# 24V_DCDC_Conv.net
KiCad netlist of a schematic drawn in Altium Designer
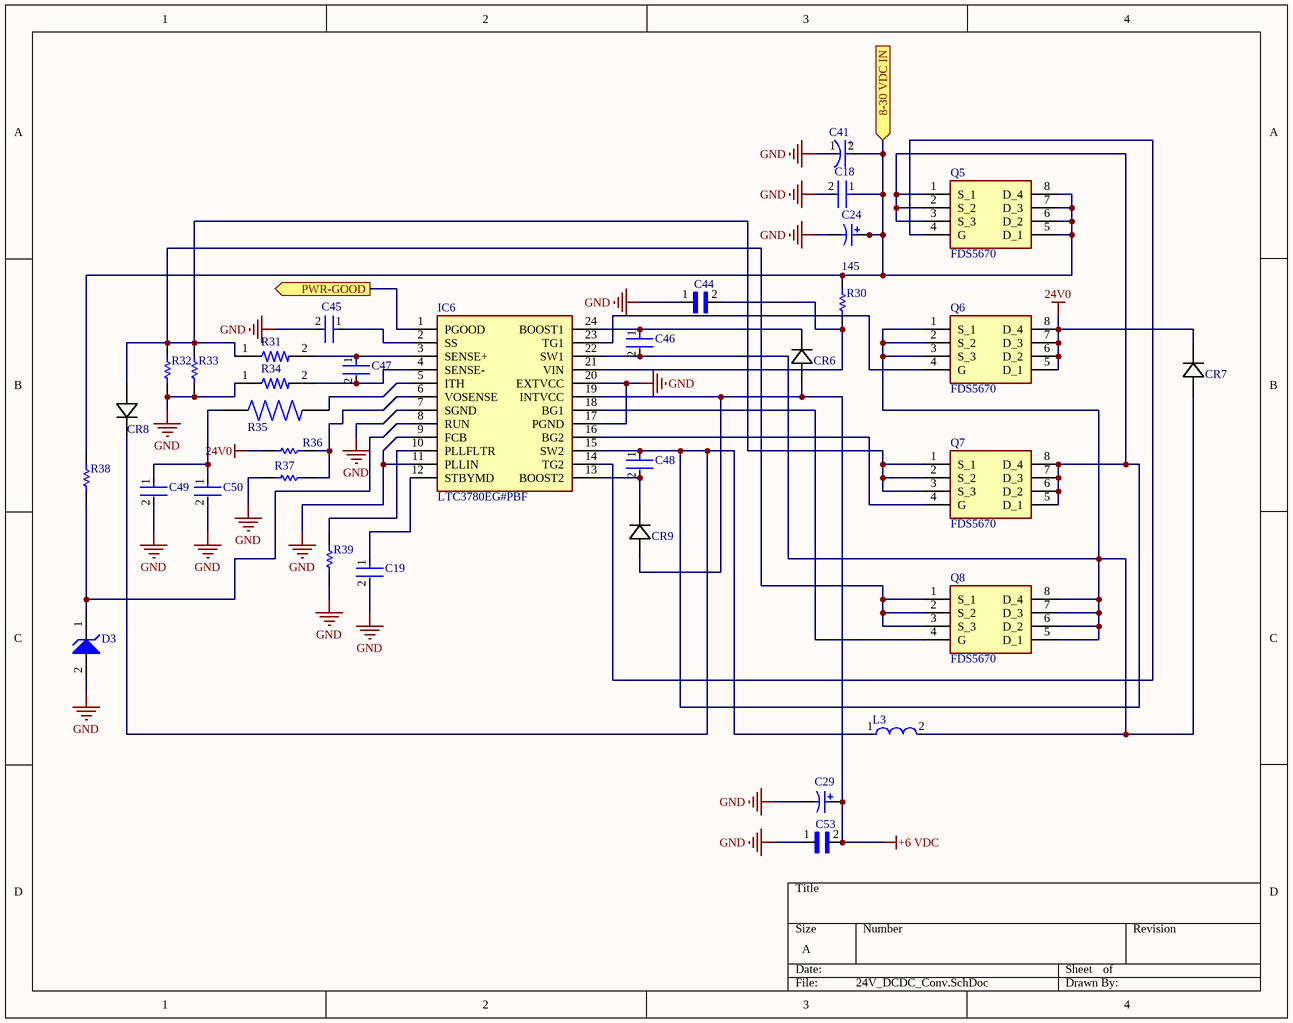
[diagram p0: 24V_DCDC_Conv.SchDoc]

(export (version "E")
  (design (tool "Eeschema 10.0.6"))
  (components
    (comp (ref "C18")
      (value "C0603C104K5RACTU")
      (footprint "FP-C0603C-CF-IPC_A")
      (description "Multilayer Ceramic Capacitors (MLCC) - SMD/SMT 50volts 0.1uF X7R 10%")
      (fields (field (name "MANUFACTURER") "KEMET") (field (name "TOLERANCE") "10%"))
      (libsource (lib "Replacements") (part "C0603C104K5RACTU"))
    )
    (comp (ref "C19")
      (value "C0603C104K5RACTU")
      (footprint "FP-C0603C-CF-IPC_A")
      (description "Multilayer Ceramic Capacitors (MLCC) - SMD/SMT 50volts 0.1uF X7R 10%")
      (fields (field (name "MANUFACTURER") "KEMET") (field (name "TOLERANCE") "10%"))
      (libsource (lib "Replacements") (part "C0603C104K5RACTU"))
    )
    (comp (ref "C24")
      (value "UUD1V220MCL1GS")
      (footprint "NIC-CAPA2-5X5.8_V")
      (description "Aluminum Electrolytic Capacitor, 22uF 35 V, UD Series 2000h 5 (Dia.) x 5.8mm")
      (fields
        (field (name "MANUFACTURER") "Nichicon")
        (field (name "TOLERANCE") "20%")
        (field (name "STOCK 1") "145")
      )
      (libsource (lib "Replacements") (part "UUD1V220MCL1GS"))
    )
    (comp (ref "C29")
      (value "UUD1V4R7MCL1GS")
      (footprint "NIC-CAPA2-4X5.8_V")
      (description "Cap Aluminum Lytic 4.7uF 35V 20% (4 X 5.8mm) SMD 80mA 2000h 105C Automotive T/R")
      (fields (field (name "MANUFACTURER") "Nichicon") (field (name "TOLERANCE") "20%"))
      (libsource (lib "Replacements") (part "UUD1V4R7MCL1GS"))
    )
    (comp (ref "C41")
      (value "EEE-HA1E221UP")
      (footprint "FP-HAF-MFG")
      (description "CAP ALUM 220UF 20% 25V SMD")
      (fields
        (field (name "VOLTAGE") "25V")
        (field (name "OCTOPART") "https://octopart.com/eee-ha1e221up-panasonic-39481261")
      )
      (libsource (lib "Altium Content Vault") (part "a00bbbee19879c290e62620ae7e47b1"))
    )
    (comp (ref "C44")
      (value "C0805C104M5UACTU")
      (footprint "CAPC2012X88N")
      (description "0.1ÂµF Â±20% 50V Ceramic Capacitor Z5U 0805 _2012 Metric_")
      (fields (field (name "MF") "KEMET"))
      (libsource (lib "0.1uF_Cap_C0805C104M5UACTU") (part "C0805C104M5UACTU"))
    )
    (comp (ref "C45")
      (value "CC0805KRX7R9BB223")
      (footprint "FP-CC0805-0_85-IPC_C")
      (description "CAP CER 0.022UF 50V X7R 0805")
      (fields
        (field (name "OCTOPART") "https://octopart.com/cc0805krx7r9bb223-yageo-39467761")
        (field (name "MANUFACTURER") "Yageo")
      )
      (libsource (lib "Altium Content Vault") (part "11868f565c42a9108669ba33697ecf6"))
    )
    (comp (ref "C46")
      (value "C0805C224K5RACTU")
      (footprint "FP-C0805C-DN-IPC_A")
      (description "CAP CER 0.22UF 50V X7R 0805")
      (fields
        (field (name "MANUFACTURER") "KEMET")
        (field (name "OCTOPART") "https://octopart.com/c0805c224k5ractu-kemet-144670")
      )
      (libsource (lib "Altium Content Vault") (part "b4654b650e69147ec39a6b967a45e02"))
    )
    (comp (ref "C47")
      (value "C1206C680J5GACTU")
      (footprint "FP-C1206C-EB-MFG")
      (description "1206 C 68pF Ceramic Multilayer Capacitor; 50 VDC; +125degC; C0G Dielec; +/-5%")
      (fields
        (field (name "OCTOPART") "https://octopart.com/c1206c680j5gactu-kemet-138975")
        (field (name "TOLERANCE") "0.05")
      )
      (libsource (lib "Altium Content Vault") (part "b4654b650e69147ec39a6b967a45e02"))
    )
    (comp (ref "C48")
      (value "C0805C224K5RACTU")
      (footprint "FP-C0805C-DN-MFG")
      (description "CAP CER 0.22UF 50V X7R 0805")
      (fields
        (field (name "MANUFACTURER") "KEMET")
        (field (name "OCTOPART") "https://octopart.com/c0805c224k5ractu-kemet-144670")
      )
      (libsource (lib "0.22uF_Cap_C0805C224K5RACTU") (part "CMP-1036-04552-2"))
    )
    (comp (ref "C49")
      (value "C1206C470J5GACTU")
      (footprint "FP-C1206C-EB-MFG")
      (description "CAP CER 47PF 50V C0G/NP0 1206")
      (fields
        (field (name "TOLERANCE") "0.05")
        (field (name "OCTOPART") "https://octopart.com/c1206c470j5gactu-kemet-96509")
      )
      (libsource (lib "47pF_Cap_C1206C470J5GACTU") (part "CMP-03020-017724-1"))
    )
    (comp (ref "C50")
      (value "CC0603KRX7R9BB103")
      (footprint "FP-CC0603-DA-IPC_B")
      (description "CAP CER 10000PF 50V X7R 0603")
      (fields (field (name "TOLERANCE") "0.1") (field (name "MANUFACTURER") "YAGEO"))
      (libsource (lib "Altium Content Vault") (part "11868f565c42a9108669ba33697ecf6"))
    )
    (comp (ref "C53")
      (value "C0805C104M5UACTU")
      (footprint "CAPC2012X88N")
      (description "0.1ÂµF Â±20% 50V Ceramic Capacitor Z5U 0805 _2012 Metric_")
      (fields (field (name "MF") "KEMET"))
      (libsource (lib "0.1uF_Cap_C0805C104M5UACTU") (part "C0805C104M5UACTU"))
    )
    (comp (ref "CR6")
      (value "SS34-E3/9AT")
      (footprint "CR_3/9AT_VIS")
      (description "No Description Available")
      (fields (field (name "COPYRIGHT") "Copyright (C) 2021 Ultra Librarian. All rights reserved."))
      (libsource (lib "SS34-E3_slash_9AT") (part "SS34-E3/9AT"))
    )
    (comp (ref "CR7")
      (value "SS34-E3/9AT")
      (footprint "CR_3/9AT_VIS")
      (description "No Description Available")
      (fields (field (name "COPYRIGHT") "Copyright (C) 2021 Ultra Librarian. All rights reserved."))
      (libsource (lib "SS34-E3_slash_9AT") (part "SS34-E3/9AT"))
    )
    (comp (ref "CR8")
      (value "SS34-E3/9AT")
      (footprint "CR_3/9AT_VIS")
      (description "No Description Available")
      (fields (field (name "COPYRIGHT") "Copyright (C) 2021 Ultra Librarian. All rights reserved."))
      (libsource (lib "SS34-E3_slash_9AT") (part "SS34-E3/9AT"))
    )
    (comp (ref "CR9")
      (value "SS34-E3/9AT")
      (footprint "CR_3/9AT_VIS")
      (description "No Description Available")
      (fields (field (name "COPYRIGHT") "Copyright (C) 2021 Ultra Librarian. All rights reserved."))
      (libsource (lib "SS34-E3_slash_9AT") (part "SS34-E3/9AT"))
    )
    (comp (ref "D3")
      (value "MMSZ4689T1G")
      (footprint "ONSC-SOD-123-2-425-04_V")
      (description "Zener Voltage Regulator, 500 mW, 2-Pin SOD-123, Pb-Free, Tape and Reel")
      (fields (field (name "MANUFACTURER") "On Semiconductor"))
      (libsource (lib "Altium Content Vault") (part "ONSC-K1A2-2"))
    )
    (comp (ref "IC6")
      (value "LTC3780EG#PBF")
      (footprint "SOP65P780X200-24N")
      (description "Integrated Circuit")
      (fields (field (name "MOUSER PART NUMBER") "584-LTC3780EG#PBF"))
      (libsource (lib "SamacSys") (part "LTC3780EG#PBF"))
    )
    (comp (ref "L3")
      (value "IHLP5050CEER4R7M01")
      (footprint "FP-IHLP-5050CE-FP_3_175x3-MFG")
      (description "Commercial Inductors, High Saturation Series 4.7uH 10A 15mΩ 20%")
      (fields (field (name "TOLERANCE") "20%"))
      (libsource (lib "Altium Content Vault") (part "725321dda6339637d4d059423bc1c3c"))
    )
    (comp (ref "Q5")
      (value "FDS5670")
      (footprint "SOIC127P600X175-8N")
      (description "MOSFET (N-Channel)")
      (fields (field (name "MOUSER PART NUMBER") "512-FDS5670"))
      (libsource (lib "SamacSys") (part "FDS5670"))
    )
    (comp (ref "Q6")
      (value "FDS5670")
      (footprint "SOIC127P600X175-8N")
      (description "MOSFET (N-Channel)")
      (fields (field (name "MOUSER PART NUMBER") "512-FDS5670"))
      (libsource (lib "SamacSys") (part "FDS5670"))
    )
    (comp (ref "Q7")
      (value "FDS5670")
      (footprint "SOIC127P600X175-8N")
      (description "MOSFET (N-Channel)")
      (fields (field (name "MOUSER PART NUMBER") "512-FDS5670"))
      (libsource (lib "SamacSys") (part "FDS5670"))
    )
    (comp (ref "Q8")
      (value "FDS5670")
      (footprint "SOIC127P600X175-8N")
      (description "MOSFET (N-Channel)")
      (fields (field (name "MOUSER PART NUMBER") "512-FDS5670"))
      (libsource (lib "SamacSys") (part "FDS5670"))
    )
    (comp (ref "R30")
      (value "ERJ3EKF1002V")
      (footprint "RESC1609X55X30LL15T15")
      (description "Chip Resistor, 10 KOhm, +/- 1%, 0.1 W, -55 to 155 degC, 0603 (1608 Metric), RoHS, Tape and Reel")
      (fields (field (name "TOLERANCE") "1%") (field (name "MANUFACTURER") "Panasonic"))
      (libsource (lib "10k_Res_ERJ-3EKF1002V") (part "CMP-1012-00623-3"))
    )
    (comp (ref "R31")
      (value "CRGS0805J100R")
      (footprint "RESC2012X65N")
      (description "100 Ohms Â±5% 0.5W, 1/2W Chip Resistor 0805 _2012 Metric_ Pulse Withstanding Thick Film")
      (fields (field (name "MF") "TE Connectivity"))
      (libsource (lib "100_Res_CRGS0805J100R") (part "CRGS0805J100R"))
    )
    (comp (ref "R32")
      (value "ERJ8BWFR018V")
      (footprint "RESC3216X70X50NL05T20")
      (fields (field (name "MANUFACTURER") "Panasonic"))
      (libsource (lib "18m_Resistor_ERJ-8BWFR018V") (part "CMP-2003-00769-1"))
    )
    (comp (ref "R33")
      (value "ERJ8BWFR018V")
      (footprint "RESC3216X70X50NL05T20")
      (fields (field (name "MANUFACTURER") "Panasonic"))
      (libsource (lib "18m_Resistor_ERJ-8BWFR018V") (part "CMP-2003-00769-1"))
    )
    (comp (ref "R34")
      (value "CRGS0805J100R")
      (footprint "RESC2012X65N")
      (description "100 Ohms Â±5% 0.5W, 1/2W Chip Resistor 0805 _2012 Metric_ Pulse Withstanding Thick Film")
      (fields (field (name "MF") "TE Connectivity"))
      (libsource (lib "100_Res_CRGS0805J100R") (part "CRGS0805J100R"))
    )
    (comp (ref "R35")
      (value "RC1206JR-07100KL")
      (footprint "RESC3116X65N")
      (description "Carbon film resistor 100 kâ„¦ SMD 1206 0.25 W 5 % 200 ppm Yageo RC1206JR-07100KL 1 pc(s)")
      (libsource (lib "100K_Res_RC1206JR-07100KL") (part "RC1206JR-07100KL"))
    )
    (comp (ref "R36")
      (value "CRCW1206294KFKEA")
      (footprint "RESC3216X60X45ML10T20")
      (fields (field (name "MANUFACTURER") "Vishay Dale"))
      (libsource (lib "Altium Content Vault") (part "RES"))
    )
    (comp (ref "R37")
      (value "ERJ3EKF1002V")
      (footprint "RESC1609X55X30LL15T15")
      (description "Chip Resistor, 10 KOhm, +/- 1%, 0.1 W, -55 to 155 degC, 0603 (1608 Metric), RoHS, Tape and Reel")
      (fields (field (name "TOLERANCE") "1%") (field (name "MANUFACTURER") "Panasonic"))
      (libsource (lib "10k_Res_ERJ-3EKF1002V") (part "CMP-1012-00623-3"))
    )
    (comp (ref "R38")
      (value "ERJ3EKF1002V")
      (footprint "RESC1609X55X30LL15T15")
      (description "Chip Resistor, 10 KOhm, +/- 1%, 0.1 W, -55 to 155 degC, 0603 (1608 Metric), RoHS, Tape and Reel")
      (fields (field (name "TOLERANCE") "1%") (field (name "MANUFACTURER") "Panasonic"))
      (libsource (lib "Altium Content Vault") (part "RES-2"))
    )
    (comp (ref "R39")
      (value "ERJ3EKF1002V")
      (footprint "RESC1609X55X30LL15T15")
      (description "Chip Resistor, 10 KOhm, +/- 1%, 0.1 W, -55 to 155 degC, 0603 (1608 Metric), RoHS, Tape and Reel")
      (fields (field (name "TOLERANCE") "1%") (field (name "MANUFACTURER") "Panasonic"))
      (libsource (lib "10k_Res_ERJ-3EKF1002V") (part "CMP-1012-00623-3"))
    )
  )
  (nets
    (net (code "1") (name "+6 VDC") (class "Default")
      (node (ref "C29") (pin "1") (pinfunction "1_1") (pintype "passive"))
      (node (ref "C53") (pin "2") (pinfunction "2_2") (pintype "passive"))
      (node (ref "CR6") (pin "1") (pinfunction "CATHODE_1") (pintype "passive"))
      (node (ref "CR9") (pin "1") (pinfunction "CATHODE_1") (pintype "passive"))
      (node (ref "IC6") (pin "19") (pinfunction "INTVCC_19") (pintype "passive"))
    )
    (net (code "2") (name "/8-30 VDC IN") (class "Default")
      (node (ref "C18") (pin "1") (pinfunction "1_1") (pintype "passive"))
      (node (ref "C24") (pin "1") (pinfunction "1_1") (pintype "passive"))
      (node (ref "C41") (pin "2") (pinfunction "A_2") (pintype "passive"))
      (node (ref "Q5") (pin "5") (pinfunction "D_1_5") (pintype "passive"))
      (node (ref "Q5") (pin "6") (pinfunction "D_2_6") (pintype "passive"))
      (node (ref "Q5") (pin "7") (pinfunction "D_3_7") (pintype "passive"))
      (node (ref "Q5") (pin "8") (pinfunction "D_4_8") (pintype "passive"))
      (node (ref "R30") (pin "1") (pinfunction "1_1") (pintype "passive"))
      (node (ref "R38") (pin "1") (pinfunction "1_1") (pintype "passive"))
    )
    (net (code "3") (name "/PWR-GOOD") (class "Default")
      (node (ref "IC6") (pin "1") (pinfunction "PGOOD_1") (pintype "passive"))
    )
    (net (code "4") (name "24V0") (class "Default")
      (node (ref "CR7") (pin "2") (pinfunction "ANODE_2") (pintype "passive"))
      (node (ref "Q6") (pin "5") (pinfunction "D_1_5") (pintype "passive"))
      (node (ref "Q6") (pin "6") (pinfunction "D_2_6") (pintype "passive"))
      (node (ref "Q6") (pin "7") (pinfunction "D_3_7") (pintype "passive"))
      (node (ref "Q6") (pin "8") (pinfunction "D_4_8") (pintype "passive"))
      (node (ref "R36") (pin "2") (pinfunction "2_2") (pintype "passive"))
    )
    (net (code "5") (name "GND") (class "Default")
      (node (ref "C18") (pin "2") (pinfunction "2_2") (pintype "passive"))
      (node (ref "C19") (pin "2") (pinfunction "2_2") (pintype "passive"))
      (node (ref "C24") (pin "2") (pinfunction "2_2") (pintype "passive"))
      (node (ref "C29") (pin "2") (pinfunction "2_2") (pintype "passive"))
      (node (ref "C41") (pin "1") (pinfunction "C_1") (pintype "passive"))
      (node (ref "C44") (pin "1") (pinfunction "1_1") (pintype "passive"))
      (node (ref "C45") (pin "2") (pinfunction "2_2") (pintype "passive"))
      (node (ref "C49") (pin "2") (pinfunction "2_2") (pintype "passive"))
      (node (ref "C50") (pin "2") (pinfunction "2_2") (pintype "passive"))
      (node (ref "C53") (pin "1") (pinfunction "1_1") (pintype "passive"))
      (node (ref "D3") (pin "2") (pinfunction "A_2") (pintype "passive"))
      (node (ref "IC6") (pin "11") (pinfunction "PLLIN_11") (pintype "passive"))
      (node (ref "IC6") (pin "17") (pinfunction "PGND_17") (pintype "passive"))
      (node (ref "IC6") (pin "20") (pinfunction "EXTVCC_20") (pintype "passive"))
      (node (ref "IC6") (pin "7") (pinfunction "SGND_7") (pintype "passive"))
      (node (ref "IC6") (pin "9") (pinfunction "FCB_9") (pintype "passive"))
      (node (ref "R32") (pin "2") (pinfunction "2_2") (pintype "passive"))
      (node (ref "R33") (pin "2") (pinfunction "2_2") (pintype "passive"))
      (node (ref "R34") (pin "1") (pinfunction "1_1") (pintype "passive"))
      (node (ref "R37") (pin "1") (pinfunction "1_1") (pintype "passive"))
      (node (ref "R39") (pin "2") (pinfunction "2_2") (pintype "passive"))
    )
    (net (code "6") (name "Net-(C49-Pad1)") (class "Default")
      (node (ref "C49") (pin "1") (pinfunction "1_1") (pintype "passive"))
      (node (ref "C50") (pin "1") (pinfunction "1_1") (pintype "passive"))
      (node (ref "R35") (pin "2") (pinfunction "2_2") (pintype "passive"))
    )
    (net (code "7") (name "Net-(CR6-ANODE)") (class "Default")
      (node (ref "C46") (pin "1") (pinfunction "1_1") (pintype "passive"))
      (node (ref "CR6") (pin "2") (pinfunction "ANODE_2") (pintype "passive"))
      (node (ref "IC6") (pin "24") (pinfunction "BOOST1_24") (pintype "passive"))
    )
    (net (code "8") (name "Net-(CR7-CATHODE)") (class "Default")
      (node (ref "C46") (pin "2") (pinfunction "2_2") (pintype "passive"))
      (node (ref "CR7") (pin "1") (pinfunction "CATHODE_1") (pintype "passive"))
      (node (ref "IC6") (pin "22") (pinfunction "SW1_22") (pintype "passive"))
      (node (ref "L3") (pin "2") (pinfunction "2_2") (pintype "passive"))
      (node (ref "Q6") (pin "1") (pinfunction "S_1_1") (pintype "passive"))
      (node (ref "Q6") (pin "2") (pinfunction "S_2_2") (pintype "passive"))
      (node (ref "Q6") (pin "3") (pinfunction "S_3_3") (pintype "passive"))
      (node (ref "Q8") (pin "5") (pinfunction "D_1_5") (pintype "passive"))
      (node (ref "Q8") (pin "6") (pinfunction "D_2_6") (pintype "passive"))
      (node (ref "Q8") (pin "7") (pinfunction "D_3_7") (pintype "passive"))
      (node (ref "Q8") (pin "8") (pinfunction "D_4_8") (pintype "passive"))
    )
    (net (code "9") (name "Net-(CR8-ANODE)") (class "Default")
      (node (ref "C48") (pin "1") (pinfunction "1_1") (pintype "passive"))
      (node (ref "CR8") (pin "2") (pinfunction "ANODE_2") (pintype "passive"))
      (node (ref "IC6") (pin "15") (pinfunction "SW2_15") (pintype "passive"))
      (node (ref "L3") (pin "1") (pinfunction "1_1") (pintype "passive"))
      (node (ref "Q5") (pin "1") (pinfunction "S_1_1") (pintype "passive"))
      (node (ref "Q5") (pin "2") (pinfunction "S_2_2") (pintype "passive"))
      (node (ref "Q5") (pin "3") (pinfunction "S_3_3") (pintype "passive"))
      (node (ref "Q7") (pin "5") (pinfunction "D_1_5") (pintype "passive"))
      (node (ref "Q7") (pin "6") (pinfunction "D_2_6") (pintype "passive"))
      (node (ref "Q7") (pin "7") (pinfunction "D_3_7") (pintype "passive"))
      (node (ref "Q7") (pin "8") (pinfunction "D_4_8") (pintype "passive"))
    )
    (net (code "10") (name "Net-(CR8-CATHODE)") (class "Default")
      (node (ref "CR8") (pin "1") (pinfunction "CATHODE_1") (pintype "passive"))
      (node (ref "Q7") (pin "1") (pinfunction "S_1_1") (pintype "passive"))
      (node (ref "Q7") (pin "2") (pinfunction "S_2_2") (pintype "passive"))
      (node (ref "Q7") (pin "3") (pinfunction "S_3_3") (pintype "passive"))
      (node (ref "Q8") (pin "1") (pinfunction "S_1_1") (pintype "passive"))
      (node (ref "Q8") (pin "2") (pinfunction "S_2_2") (pintype "passive"))
      (node (ref "Q8") (pin "3") (pinfunction "S_3_3") (pintype "passive"))
      (node (ref "R31") (pin "1") (pinfunction "1_1") (pintype "passive"))
      (node (ref "R32") (pin "1") (pinfunction "1_1") (pintype "passive"))
      (node (ref "R33") (pin "1") (pinfunction "1_1") (pintype "passive"))
    )
    (net (code "11") (name "Net-(CR9-ANODE)") (class "Default")
      (node (ref "C48") (pin "2") (pinfunction "2_2") (pintype "passive"))
      (node (ref "CR9") (pin "2") (pinfunction "ANODE_2") (pintype "passive"))
      (node (ref "IC6") (pin "13") (pinfunction "BOOST2_13") (pintype "passive"))
    )
    (net (code "12") (name "Net-(D3-K)") (class "Default")
      (node (ref "D3") (pin "1") (pinfunction "K_1") (pintype "passive"))
      (node (ref "IC6") (pin "8") (pinfunction "RUN_8") (pintype "passive"))
      (node (ref "R38") (pin "2") (pinfunction "2_2") (pintype "passive"))
    )
    (net (code "13") (name "Net-(IC6-BG1)") (class "Default")
      (node (ref "IC6") (pin "18") (pinfunction "BG1_18") (pintype "passive"))
      (node (ref "Q8") (pin "4") (pinfunction "G_4") (pintype "passive"))
    )
    (net (code "14") (name "Net-(IC6-BG2)") (class "Default")
      (node (ref "IC6") (pin "16") (pinfunction "BG2_16") (pintype "passive"))
      (node (ref "Q7") (pin "4") (pinfunction "G_4") (pintype "passive"))
    )
    (net (code "15") (name "Net-(IC6-ITH)") (class "Default")
      (node (ref "IC6") (pin "5") (pinfunction "ITH_5") (pintype "passive"))
      (node (ref "R35") (pin "1") (pinfunction "1_1") (pintype "passive"))
    )
    (net (code "16") (name "Net-(IC6-PLLFLTR)") (class "Default")
      (node (ref "IC6") (pin "10") (pinfunction "PLLFLTR_10") (pintype "passive"))
      (node (ref "R39") (pin "1") (pinfunction "1_1") (pintype "passive"))
    )
    (net (code "17") (name "Net-(IC6-SENSE+)") (class "Default")
      (node (ref "C47") (pin "1") (pinfunction "1_1") (pintype "passive"))
      (node (ref "IC6") (pin "3") (pinfunction "SENSE+_3") (pintype "passive"))
      (node (ref "R31") (pin "2") (pinfunction "2_2") (pintype "passive"))
    )
    (net (code "18") (name "Net-(IC6-SENSE-)") (class "Default")
      (node (ref "C47") (pin "2") (pinfunction "2_2") (pintype "passive"))
      (node (ref "IC6") (pin "4") (pinfunction "SENSE-_4") (pintype "passive"))
      (node (ref "R34") (pin "2") (pinfunction "2_2") (pintype "passive"))
    )
    (net (code "19") (name "Net-(IC6-SS)") (class "Default")
      (node (ref "C45") (pin "1") (pinfunction "1_1") (pintype "passive"))
      (node (ref "IC6") (pin "2") (pinfunction "SS_2") (pintype "passive"))
    )
    (net (code "20") (name "Net-(IC6-STBYMD)") (class "Default")
      (node (ref "C19") (pin "1") (pinfunction "1_1") (pintype "passive"))
      (node (ref "IC6") (pin "12") (pinfunction "STBYMD_12") (pintype "passive"))
    )
    (net (code "21") (name "Net-(IC6-TG1)") (class "Default")
      (node (ref "IC6") (pin "23") (pinfunction "TG1_23") (pintype "passive"))
      (node (ref "Q6") (pin "4") (pinfunction "G_4") (pintype "passive"))
    )
    (net (code "22") (name "Net-(IC6-TG2)") (class "Default")
      (node (ref "IC6") (pin "14") (pinfunction "TG2_14") (pintype "passive"))
      (node (ref "Q5") (pin "4") (pinfunction "G_4") (pintype "passive"))
    )
    (net (code "23") (name "Net-(IC6-VIN)") (class "Default")
      (node (ref "C44") (pin "2") (pinfunction "2_2") (pintype "passive"))
      (node (ref "IC6") (pin "21") (pinfunction "VIN_21") (pintype "passive"))
      (node (ref "R30") (pin "2") (pinfunction "2_2") (pintype "passive"))
    )
    (net (code "24") (name "Net-(IC6-VOSENSE)") (class "Default")
      (node (ref "IC6") (pin "6") (pinfunction "VOSENSE_6") (pintype "passive"))
      (node (ref "R36") (pin "1") (pinfunction "1_1") (pintype "passive"))
      (node (ref "R37") (pin "2") (pinfunction "2_2") (pintype "passive"))
    )
  )
)
